# joystick.net
KiCad netlist of a schematic drawn in Altium Designer
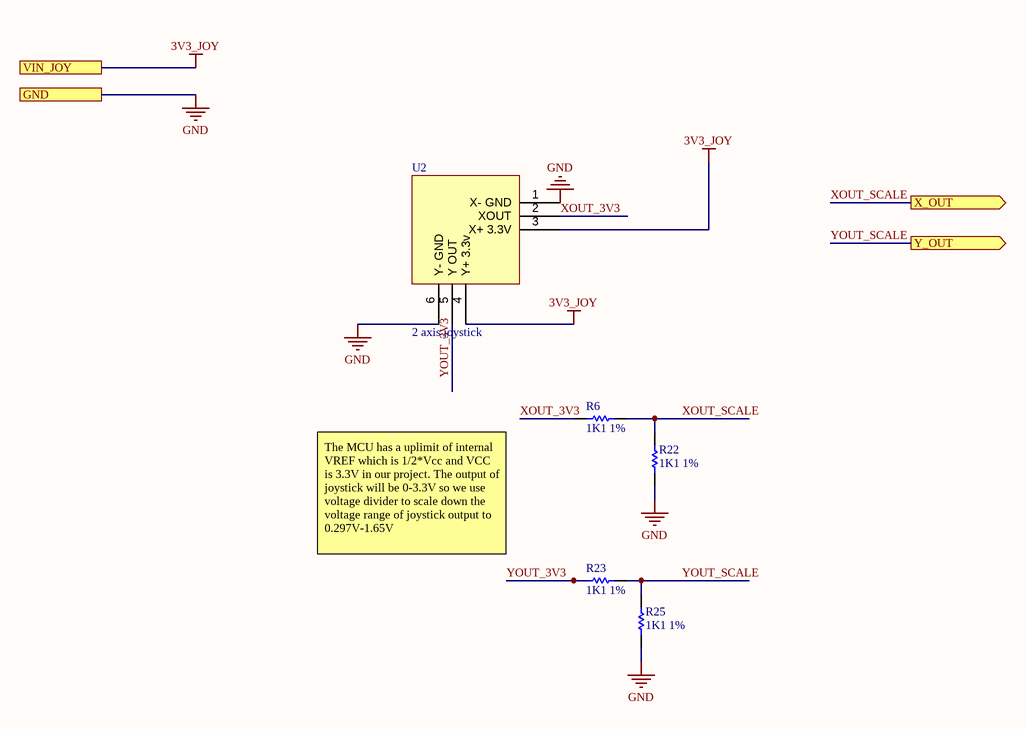
[diagram p0: joystick.SchDoc]

(export (version "E")
  (design (tool "Eeschema 10.0.6"))
  (components
    (comp (ref "R6")
      (value "1K1 1%")
      (footprint "RESC0603(1608)_N")
      (description "1K1 0.1W 1% 0603 (1608 Metric)  SMD")
      (fields (field (name "TOLERANCE") "1 %") (field (name "POWER") "0.1 W"))
      (libsource (lib "Altium Content Vault") (part "RES"))
    )
    (comp (ref "R22")
      (value "1K1 1%")
      (footprint "RESC0603(1608)_N")
      (description "1K1 0.1W 1% 0603 (1608 Metric)  SMD")
      (fields (field (name "TOLERANCE") "1 %") (field (name "POWER") "0.1 W"))
      (libsource (lib "Altium Content Vault") (part "RES"))
    )
    (comp (ref "R23")
      (value "1K1 1%")
      (footprint "RESC0603(1608)_N")
      (description "1K1 0.1W 1% 0603 (1608 Metric)  SMD")
      (fields (field (name "TOLERANCE") "1 %") (field (name "POWER") "0.1 W"))
      (libsource (lib "Altium Content Vault") (part "RES"))
    )
    (comp (ref "R25")
      (value "1K1 1%")
      (footprint "RESC0603(1608)_N")
      (description "1K1 0.1W 1% 0603 (1608 Metric)  SMD")
      (fields (field (name "TOLERANCE") "1 %") (field (name "POWER") "0.1 W"))
      (libsource (lib "Altium Content Vault") (part "RES"))
    )
    (comp (ref "U2")
      (value "2 axis joystick")
      (footprint "JOYSTICK")
      (description "JOYSTICK 10K OHM 2 AXIS TH")
      (fields
        (field (name "MANUFACTURER") "Adafruit Industries")
        (field (name "MANUFACTURER PART NUMBER") "2765")
      )
      (libsource (lib "joystick") (part "Adafruit 2765"))
    )
  )
  (nets
    (net (code "1") (name "/XOUT_3V3") (class "Default")
      (node (ref "R6") (pin "1") (pinfunction "1_1") (pintype "passive"))
      (node (ref "U2") (pin "2") (pinfunction "XOUT_2") (pintype "passive"))
    )
    (net (code "2") (name "/XOUT_SCALE") (class "Default")
      (node (ref "R22") (pin "2") (pinfunction "2_2") (pintype "passive"))
      (node (ref "R6") (pin "2") (pinfunction "2_2") (pintype "passive"))
    )
    (net (code "3") (name "/YOUT_3V3") (class "Default")
      (node (ref "R23") (pin "1") (pinfunction "1_1") (pintype "passive"))
      (node (ref "U2") (pin "5") (pinfunction "Y_OUT_5") (pintype "passive"))
    )
    (net (code "4") (name "/YOUT_SCALE") (class "Default")
      (node (ref "R23") (pin "2") (pinfunction "2_2") (pintype "passive"))
      (node (ref "R25") (pin "2") (pinfunction "2_2") (pintype "passive"))
    )
    (net (code "5") (name "3V3_JOY") (class "Default")
      (node (ref "U2") (pin "3") (pinfunction "X+_3.3V_3") (pintype "passive"))
      (node (ref "U2") (pin "4") (pinfunction "Y+_3.3v_4") (pintype "passive"))
    )
    (net (code "6") (name "GND") (class "Default")
      (node (ref "R22") (pin "1") (pinfunction "1_1") (pintype "passive"))
      (node (ref "R25") (pin "1") (pinfunction "1_1") (pintype "passive"))
      (node (ref "U2") (pin "1") (pinfunction "X-_GND_1") (pintype "passive"))
      (node (ref "U2") (pin "6") (pinfunction "Y-_GND_6") (pintype "passive"))
    )
  )
)
